# 10_HDMI.net
KiCad netlist of a schematic drawn in Altium Designer
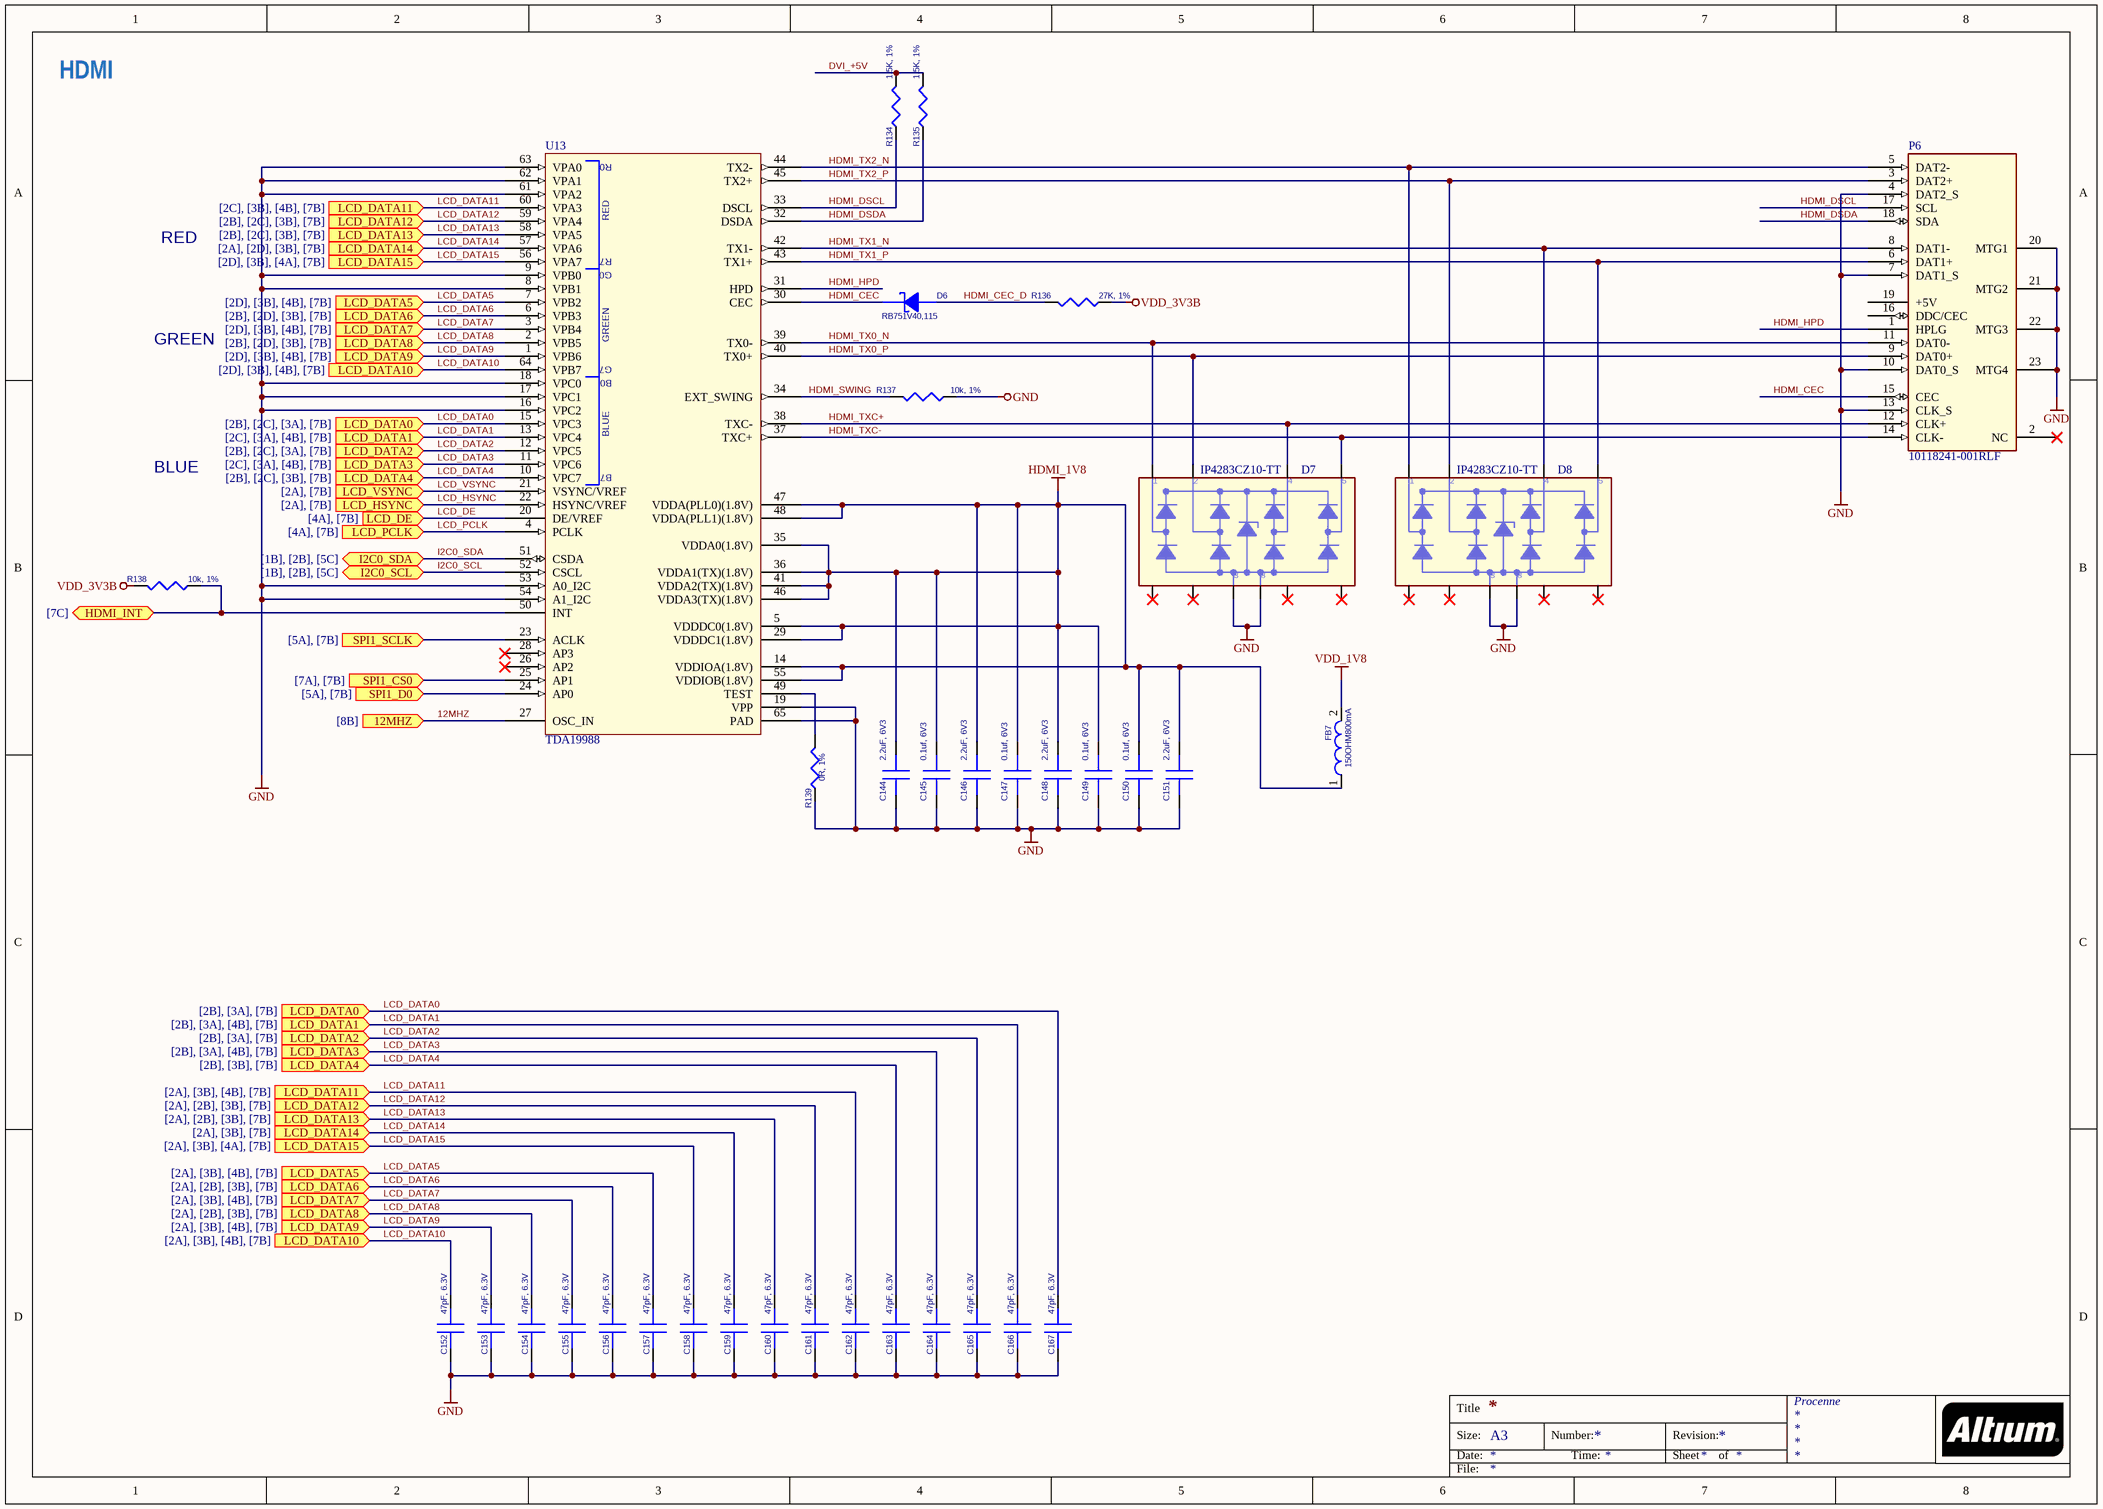
[diagram p0: 10_HDMI.SchDoc]

(export (version "E")
  (design (tool "Eeschema 10.0.6"))
  (components
    (comp (ref "C144")
      (value "2.2uF, 6V3")
      (footprint "402")
      (description "CAP CER 2.2UF 6.3V 10% X5R 0402")
      (fields
        (field (name "MANUFACTURER") "TDK Corporation")
        (field (name "MANUFACTURER PART NUMBER") "C1005X5R0J225K050BC")
      )
      (libsource (lib "BEAGLEBONEBLACK_REV A5B") (part "CAP SMD"))
    )
    (comp (ref "C145")
      (value "0.1uf, 6V3")
      (footprint "402")
      (description "CAP CER 0.1UF 6.3V 10% X5R 0402")
      (fields
        (field (name "MANUFACTURER") "TDK Corporation")
        (field (name "MANUFACTURER PART NUMBER") "C1005X5R0J104K050BA")
      )
      (libsource (lib "BEAGLEBONEBLACK_REV A5B") (part "CAP SMD"))
    )
    (comp (ref "C146")
      (value "2.2uF, 6V3")
      (footprint "402")
      (description "CAP CER 2.2UF 6.3V 10% X5R 0402")
      (fields
        (field (name "MANUFACTURER") "TDK Corporation")
        (field (name "MANUFACTURER PART NUMBER") "C1005X5R0J225K050BC")
      )
      (libsource (lib "BEAGLEBONEBLACK_REV A5B") (part "CAP SMD"))
    )
    (comp (ref "C147")
      (value "0.1uf, 6V3")
      (footprint "402")
      (description "CAP CER 0.1UF 6.3V 10% X5R 0402")
      (fields
        (field (name "MANUFACTURER") "TDK Corporation")
        (field (name "MANUFACTURER PART NUMBER") "C1005X5R0J104K050BA")
      )
      (libsource (lib "BEAGLEBONEBLACK_REV A5B") (part "CAP SMD"))
    )
    (comp (ref "C148")
      (value "2.2uF, 6V3")
      (footprint "402")
      (description "CAP CER 2.2UF 6.3V 10% X5R 0402")
      (fields
        (field (name "MANUFACTURER") "TDK Corporation")
        (field (name "MANUFACTURER PART NUMBER") "C1005X5R0J225K050BC")
      )
      (libsource (lib "BEAGLEBONEBLACK_REV A5B") (part "CAP SMD"))
    )
    (comp (ref "C149")
      (value "0.1uf, 6V3")
      (footprint "402")
      (description "CAP CER 0.1UF 6.3V 10% X5R 0402")
      (fields
        (field (name "MANUFACTURER") "TDK Corporation")
        (field (name "MANUFACTURER PART NUMBER") "C1005X5R0J104K050BA")
      )
      (libsource (lib "BEAGLEBONEBLACK_REV A5B") (part "CAP SMD"))
    )
    (comp (ref "C150")
      (value "0.1uf, 6V3")
      (footprint "402")
      (description "CAP CER 0.1UF 6.3V 10% X5R 0402")
      (fields
        (field (name "MANUFACTURER") "TDK Corporation")
        (field (name "MANUFACTURER PART NUMBER") "C1005X5R0J104K050BA")
      )
      (libsource (lib "BEAGLEBONEBLACK_REV A5B") (part "CAP SMD"))
    )
    (comp (ref "C151")
      (value "2.2uF, 6V3")
      (footprint "402")
      (description "CAP CER 2.2UF 6.3V 10% X5R 0402")
      (fields
        (field (name "MANUFACTURER") "TDK Corporation")
        (field (name "MANUFACTURER PART NUMBER") "C1005X5R0J225K050BC")
      )
      (libsource (lib "BEAGLEBONEBLACK_REV A5B") (part "CAP SMD"))
    )
    (comp (ref "C152")
      (value "47pF, 6.3V")
      (footprint "402")
      (description "CAP CER 47PF 50V 5% NP0 0402")
      (fields
        (field (name "MANUFACTURER") "TDK Corporation")
        (field (name "MANUFACTURER PART NUMBER") "C1005C0G1H470J050BA")
      )
      (libsource (lib "BEAGLEBONEBLACK_REV A5B") (part "CAP SMD"))
    )
    (comp (ref "C153")
      (value "47pF, 6.3V")
      (footprint "402")
      (description "CAP CER 47PF 50V 5% NP0 0402")
      (fields
        (field (name "MANUFACTURER") "TDK Corporation")
        (field (name "MANUFACTURER PART NUMBER") "C1005C0G1H470J050BA")
      )
      (libsource (lib "BEAGLEBONEBLACK_REV A5B") (part "CAP SMD"))
    )
    (comp (ref "C154")
      (value "47pF, 6.3V")
      (footprint "402")
      (description "CAP CER 47PF 50V 5% NP0 0402")
      (fields
        (field (name "MANUFACTURER") "TDK Corporation")
        (field (name "MANUFACTURER PART NUMBER") "C1005C0G1H470J050BA")
      )
      (libsource (lib "BEAGLEBONEBLACK_REV A5B") (part "CAP SMD"))
    )
    (comp (ref "C155")
      (value "47pF, 6.3V")
      (footprint "402")
      (description "CAP CER 47PF 50V 5% NP0 0402")
      (fields
        (field (name "MANUFACTURER") "TDK Corporation")
        (field (name "MANUFACTURER PART NUMBER") "C1005C0G1H470J050BA")
      )
      (libsource (lib "BEAGLEBONEBLACK_REV A5B") (part "CAP SMD"))
    )
    (comp (ref "C156")
      (value "47pF, 6.3V")
      (footprint "402")
      (description "CAP CER 47PF 50V 5% NP0 0402")
      (fields
        (field (name "MANUFACTURER") "TDK Corporation")
        (field (name "MANUFACTURER PART NUMBER") "C1005C0G1H470J050BA")
      )
      (libsource (lib "BEAGLEBONEBLACK_REV A5B") (part "CAP SMD"))
    )
    (comp (ref "C157")
      (value "47pF, 6.3V")
      (footprint "402")
      (description "CAP CER 47PF 50V 5% NP0 0402")
      (fields
        (field (name "MANUFACTURER") "TDK Corporation")
        (field (name "MANUFACTURER PART NUMBER") "C1005C0G1H470J050BA")
      )
      (libsource (lib "BEAGLEBONEBLACK_REV A5B") (part "CAP SMD"))
    )
    (comp (ref "C158")
      (value "47pF, 6.3V")
      (footprint "402")
      (description "CAP CER 47PF 50V 5% NP0 0402")
      (fields
        (field (name "MANUFACTURER") "TDK Corporation")
        (field (name "MANUFACTURER PART NUMBER") "C1005C0G1H470J050BA")
      )
      (libsource (lib "BEAGLEBONEBLACK_REV A5B") (part "CAP SMD"))
    )
    (comp (ref "C159")
      (value "47pF, 6.3V")
      (footprint "402")
      (description "CAP CER 47PF 50V 5% NP0 0402")
      (fields
        (field (name "MANUFACTURER") "TDK Corporation")
        (field (name "MANUFACTURER PART NUMBER") "C1005C0G1H470J050BA")
      )
      (libsource (lib "BEAGLEBONEBLACK_REV A5B") (part "CAP SMD"))
    )
    (comp (ref "C160")
      (value "47pF, 6.3V")
      (footprint "402")
      (description "CAP CER 47PF 50V 5% NP0 0402")
      (fields
        (field (name "MANUFACTURER") "TDK Corporation")
        (field (name "MANUFACTURER PART NUMBER") "C1005C0G1H470J050BA")
      )
      (libsource (lib "BEAGLEBONEBLACK_REV A5B") (part "CAP SMD"))
    )
    (comp (ref "C161")
      (value "47pF, 6.3V")
      (footprint "402")
      (description "CAP CER 47PF 50V 5% NP0 0402")
      (fields
        (field (name "MANUFACTURER") "TDK Corporation")
        (field (name "MANUFACTURER PART NUMBER") "C1005C0G1H470J050BA")
      )
      (libsource (lib "BEAGLEBONEBLACK_REV A5B") (part "CAP SMD"))
    )
    (comp (ref "C162")
      (value "47pF, 6.3V")
      (footprint "402")
      (description "CAP CER 47PF 50V 5% NP0 0402")
      (fields
        (field (name "MANUFACTURER") "TDK Corporation")
        (field (name "MANUFACTURER PART NUMBER") "C1005C0G1H470J050BA")
      )
      (libsource (lib "BEAGLEBONEBLACK_REV A5B") (part "CAP SMD"))
    )
    (comp (ref "C163")
      (value "47pF, 6.3V")
      (footprint "402")
      (description "CAP CER 47PF 50V 5% NP0 0402")
      (fields
        (field (name "MANUFACTURER") "TDK Corporation")
        (field (name "MANUFACTURER PART NUMBER") "C1005C0G1H470J050BA")
      )
      (libsource (lib "BEAGLEBONEBLACK_REV A5B") (part "CAP SMD"))
    )
    (comp (ref "C164")
      (value "47pF, 6.3V")
      (footprint "402")
      (description "CAP CER 47PF 50V 5% NP0 0402")
      (fields
        (field (name "MANUFACTURER") "TDK Corporation")
        (field (name "MANUFACTURER PART NUMBER") "C1005C0G1H470J050BA")
      )
      (libsource (lib "BEAGLEBONEBLACK_REV A5B") (part "CAP SMD"))
    )
    (comp (ref "C165")
      (value "47pF, 6.3V")
      (footprint "402")
      (description "CAP CER 47PF 50V 5% NP0 0402")
      (fields
        (field (name "MANUFACTURER") "TDK Corporation")
        (field (name "MANUFACTURER PART NUMBER") "C1005C0G1H470J050BA")
      )
      (libsource (lib "BEAGLEBONEBLACK_REV A5B") (part "CAP SMD"))
    )
    (comp (ref "C166")
      (value "47pF, 6.3V")
      (footprint "402")
      (description "CAP CER 47PF 50V 5% NP0 0402")
      (fields
        (field (name "MANUFACTURER") "TDK Corporation")
        (field (name "MANUFACTURER PART NUMBER") "C1005C0G1H470J050BA")
      )
      (libsource (lib "BEAGLEBONEBLACK_REV A5B") (part "CAP SMD"))
    )
    (comp (ref "C167")
      (value "47pF, 6.3V")
      (footprint "402")
      (description "CAP CER 47PF 50V 5% NP0 0402")
      (fields
        (field (name "MANUFACTURER") "TDK Corporation")
        (field (name "MANUFACTURER PART NUMBER") "C1005C0G1H470J050BA")
      )
      (libsource (lib "BEAGLEBONEBLACK_REV A5B") (part "CAP SMD"))
    )
    (comp (ref "D6")
      (value "RB751V40,115")
      (footprint "SOD323")
      (description "DIODE SCHOTTKY 40V 120MA SOD323")
      (fields (field (name "MANUFACTURER") "NXP Semiconductors"))
      (libsource (lib "BEAGLEBONEBLACK_REV A5B") (part "Zener"))
    )
    (comp (ref "D7")
      (value "IP4283CZ10-TT")
      (footprint "TSSOP10")
      (description "DIODE ESD PROT HDMI 10TSSOP")
      (fields
        (field (name "MANUFACTURER") "NXP Semiconductors")
        (field (name "MANUFACTURER PART NUMBER") "IP4283CZ10-TT,118")
      )
      (libsource (lib "BEAGLEBONEBLACK_REV A5B") (part "32CTQ030/TO_1"))
    )
    (comp (ref "D8")
      (value "IP4283CZ10-TT")
      (footprint "TSSOP10")
      (description "DIODE ESD PROT HDMI 10TSSOP")
      (fields
        (field (name "MANUFACTURER") "NXP Semiconductors")
        (field (name "MANUFACTURER PART NUMBER") "IP4283CZ10-TT,118")
      )
      (libsource (lib "BEAGLEBONEBLACK_REV A5B") (part "32CTQ030/TO_1"))
    )
    (comp (ref "FB7")
      (value "150OHM800mA")
      (footprint "SM-7351-IND-0805")
      (description "FERRITE 800MA 150 OHM 0805 SMD")
      (fields
        (field (name "MANUFACTURER") "Laird-Signal Integrity Products")
        (field (name "MANUFACTURER PART NUMBER") "LI0805H151R-10")
      )
      (libsource (lib "BEAGLEBONEBLACK_REV A5B") (part "IND"))
    )
    (comp (ref "P6")
      (value "10118241-001RLF")
      (footprint "CONN19_HDMI")
      (description "CONN HDMI RECPT 19POS SMT R/A")
      (fields (field (name "MANUFACTURER") "FCI"))
      (libsource (lib "BEAGLEBONEBLACK_REV A5B") (part "Micro HDMI"))
    )
    (comp (ref "R134")
      (value "1.5K, 1%")
      (footprint "402")
      (description "RES 1.50K OHM 1/16W 1% 0402 SMD")
      (fields
        (field (name "MANUFACTURER") "Yageo")
        (field (name "MANUFACTURER PART NUMBER") "RC0402FR-071K5L")
      )
      (libsource (lib "BEAGLEBONEBLACK_REV A5B") (part "RES SMD"))
    )
    (comp (ref "R135")
      (value "1.5K, 1%")
      (footprint "402")
      (description "RES 1.50K OHM 1/16W 1% 0402 SMD")
      (fields
        (field (name "MANUFACTURER") "Yageo")
        (field (name "MANUFACTURER PART NUMBER") "RC0402FR-071K5L")
      )
      (libsource (lib "BEAGLEBONEBLACK_REV A5B") (part "RES SMD"))
    )
    (comp (ref "R136")
      (value "27K, 1%")
      (footprint "402")
      (description "RES 27.0K OHM 1/16W 1% 0402 SMD")
      (fields
        (field (name "MANUFACTURER") "Yageo")
        (field (name "MANUFACTURER PART NUMBER") "RC0402FR-0727KL")
      )
      (libsource (lib "BEAGLEBONEBLACK_REV A5B") (part "RES SMD"))
    )
    (comp (ref "R137")
      (value "10k, 1%")
      (footprint "402")
      (description "RES 10K OHM 1/16W 5% 0402 SMD")
      (fields
        (field (name "MANUFACTURER") "Rohm Semiconductor")
        (field (name "MANUFACTURER PART NUMBER") "MCR01MZPJ103")
      )
      (libsource (lib "BEAGLEBONEBLACK_REV A5B") (part "RES SMD"))
    )
    (comp (ref "R138")
      (value "10k, 1%")
      (footprint "402")
      (description "RES 10K OHM 1/16W 5% 0402 SMD")
      (fields
        (field (name "MANUFACTURER") "Rohm Semiconductor")
        (field (name "MANUFACTURER PART NUMBER") "MCR01MZPJ103")
      )
      (libsource (lib "BEAGLEBONEBLACK_REV A5B") (part "RES SMD"))
    )
    (comp (ref "R139")
      (value "0R, 1%")
      (footprint "402")
      (description "RES 0.0 OHM 1/16W 0402 SMD")
      (fields
        (field (name "MANUFACTURER") "Yageo")
        (field (name "MANUFACTURER PART NUMBER") "RC0402JR-070RL")
      )
      (libsource (lib "BEAGLEBONEBLACK_REV A5B") (part "RES SMD"))
    )
    (comp (ref "U13")
      (value "TDA19988")
      (footprint "QFN64S9X9P5")
      (description "IC HDMI TRANSMITTER 64-HVQFN")
      (fields
        (field (name "MANUFACTURER") "NXP Semiconductors")
        (field (name "MANUFACTURER PART NUMBER") "TDA19988AHN/C1,551")
      )
      (libsource (lib "BEAGLEBONEBLACK_REV A5B") (part "TDA19988"))
    )
  )
  (nets
    (net (code "1") (name "/12MHZ") (class "Default")
      (node (ref "U13") (pin "27") (pinfunction "OSC_IN_27") (pintype "passive"))
    )
    (net (code "2") (name "/DVI_+5V") (class "Default")
      (node (ref "R134") (pin "1") (pinfunction "P1_1") (pintype "passive"))
      (node (ref "R135") (pin "1") (pinfunction "P1_1") (pintype "passive"))
    )
    (net (code "3") (name "/HDMI_CEC") (class "Default")
      (node (ref "D6") (pin "1") (pinfunction "C_1") (pintype "passive"))
      (node (ref "P6") (pin "15") (pinfunction "CEC_15") (pintype "bidirectional"))
      (node (ref "U13") (pin "30") (pinfunction "CEC_30") (pintype "output"))
    )
    (net (code "4") (name "/HDMI_CEC_D") (class "Default")
      (node (ref "D6") (pin "2") (pinfunction "A_2") (pintype "passive"))
      (node (ref "R136") (pin "1") (pinfunction "P1_1") (pintype "passive"))
    )
    (net (code "5") (name "/HDMI_DSCL") (class "Default")
      (node (ref "P6") (pin "17") (pinfunction "SCL_17") (pintype "input"))
      (node (ref "R134") (pin "2") (pinfunction "P2_2") (pintype "passive"))
      (node (ref "U13") (pin "33") (pinfunction "DSCL_33") (pintype "output"))
    )
    (net (code "6") (name "/HDMI_DSDA") (class "Default")
      (node (ref "P6") (pin "18") (pinfunction "SDA_18") (pintype "bidirectional"))
      (node (ref "R135") (pin "2") (pinfunction "P2_2") (pintype "passive"))
      (node (ref "U13") (pin "32") (pinfunction "DSDA_32") (pintype "output"))
    )
    (net (code "7") (name "/HDMI_HPD") (class "Default")
      (node (ref "P6") (pin "1") (pinfunction "HPLG_1") (pintype "passive"))
      (node (ref "U13") (pin "31") (pinfunction "HPD_31") (pintype "output"))
    )
    (net (code "8") (name "/HDMI_INT") (class "Default")
      (node (ref "R138") (pin "2") (pinfunction "P2_2") (pintype "passive"))
      (node (ref "U13") (pin "50") (pinfunction "INT_50") (pintype "open_collector"))
    )
    (net (code "9") (name "/HDMI_SWING") (class "Default")
      (node (ref "R137") (pin "1") (pinfunction "P1_1") (pintype "passive"))
      (node (ref "U13") (pin "34") (pinfunction "EXT_SWING_34") (pintype "output"))
    )
    (net (code "10") (name "/HDMI_TX0_N") (class "Default")
      (node (ref "D7") (pin "1") (pinfunction "1_1") (pintype "passive"))
      (node (ref "P6") (pin "11") (pinfunction "DAT0-_11") (pintype "input"))
      (node (ref "U13") (pin "39") (pinfunction "TX0-_39") (pintype "output"))
    )
    (net (code "11") (name "/HDMI_TX0_P") (class "Default")
      (node (ref "D7") (pin "2") (pinfunction "2_2") (pintype "passive"))
      (node (ref "P6") (pin "9") (pinfunction "DAT0+_9") (pintype "input"))
      (node (ref "U13") (pin "40") (pinfunction "TX0+_40") (pintype "output"))
    )
    (net (code "12") (name "/HDMI_TX1_N") (class "Default")
      (node (ref "D8") (pin "4") (pinfunction "4_4") (pintype "passive"))
      (node (ref "P6") (pin "8") (pinfunction "DAT1-_8") (pintype "input"))
      (node (ref "U13") (pin "42") (pinfunction "TX1-_42") (pintype "output"))
    )
    (net (code "13") (name "/HDMI_TX1_P") (class "Default")
      (node (ref "D8") (pin "5") (pinfunction "5_5") (pintype "passive"))
      (node (ref "P6") (pin "6") (pinfunction "DAT1+_6") (pintype "input"))
      (node (ref "U13") (pin "43") (pinfunction "TX1+_43") (pintype "output"))
    )
    (net (code "14") (name "/HDMI_TX2_N") (class "Default")
      (node (ref "D8") (pin "1") (pinfunction "1_1") (pintype "passive"))
      (node (ref "P6") (pin "5") (pinfunction "DAT2-_5") (pintype "input"))
      (node (ref "U13") (pin "44") (pinfunction "TX2-_44") (pintype "output"))
    )
    (net (code "15") (name "/HDMI_TX2_P") (class "Default")
      (node (ref "D8") (pin "2") (pinfunction "2_2") (pintype "passive"))
      (node (ref "P6") (pin "3") (pinfunction "DAT2+_3") (pintype "input"))
      (node (ref "U13") (pin "45") (pinfunction "TX2+_45") (pintype "output"))
    )
    (net (code "16") (name "/HDMI_TXC+") (class "Default")
      (node (ref "D7") (pin "4") (pinfunction "4_4") (pintype "passive"))
      (node (ref "P6") (pin "12") (pinfunction "CLK+_12") (pintype "input"))
      (node (ref "U13") (pin "38") (pinfunction "TXC-_38") (pintype "output"))
    )
    (net (code "17") (name "/HDMI_TXC-") (class "Default")
      (node (ref "D7") (pin "5") (pinfunction "5_5") (pintype "passive"))
      (node (ref "P6") (pin "14") (pinfunction "CLK-_14") (pintype "input"))
      (node (ref "U13") (pin "37") (pinfunction "TXC+_37") (pintype "output"))
    )
    (net (code "18") (name "/I2C0_SCL") (class "Default")
      (node (ref "U13") (pin "52") (pinfunction "CSCL_52") (pintype "input"))
    )
    (net (code "19") (name "/I2C0_SDA") (class "Default")
      (node (ref "U13") (pin "51") (pinfunction "CSDA_51") (pintype "bidirectional"))
    )
    (net (code "20") (name "/LCD_DATA0") (class "Default")
      (node (ref "C167") (pin "1") (pinfunction "1_1") (pintype "passive"))
      (node (ref "U13") (pin "15") (pinfunction "VPC3_15") (pintype "input"))
    )
    (net (code "21") (name "/LCD_DATA1") (class "Default")
      (node (ref "C166") (pin "1") (pinfunction "1_1") (pintype "passive"))
      (node (ref "U13") (pin "13") (pinfunction "VPC4_13") (pintype "input"))
    )
    (net (code "22") (name "/LCD_DATA2") (class "Default")
      (node (ref "C165") (pin "1") (pinfunction "1_1") (pintype "passive"))
      (node (ref "U13") (pin "12") (pinfunction "VPC5_12") (pintype "input"))
    )
    (net (code "23") (name "/LCD_DATA3") (class "Default")
      (node (ref "C164") (pin "1") (pinfunction "1_1") (pintype "passive"))
      (node (ref "U13") (pin "11") (pinfunction "VPC6_11") (pintype "input"))
    )
    (net (code "24") (name "/LCD_DATA4") (class "Default")
      (node (ref "C163") (pin "1") (pinfunction "1_1") (pintype "passive"))
      (node (ref "U13") (pin "10") (pinfunction "VPC7_10") (pintype "input"))
    )
    (net (code "25") (name "/LCD_DATA5") (class "Default")
      (node (ref "C157") (pin "1") (pinfunction "1_1") (pintype "passive"))
      (node (ref "U13") (pin "7") (pinfunction "VPB2_7") (pintype "input"))
    )
    (net (code "26") (name "/LCD_DATA6") (class "Default")
      (node (ref "C156") (pin "1") (pinfunction "1_1") (pintype "passive"))
      (node (ref "U13") (pin "6") (pinfunction "VPB3_6") (pintype "input"))
    )
    (net (code "27") (name "/LCD_DATA7") (class "Default")
      (node (ref "C155") (pin "1") (pinfunction "1_1") (pintype "passive"))
      (node (ref "U13") (pin "3") (pinfunction "VPB4_3") (pintype "input"))
    )
    (net (code "28") (name "/LCD_DATA8") (class "Default")
      (node (ref "C154") (pin "1") (pinfunction "1_1") (pintype "passive"))
      (node (ref "U13") (pin "2") (pinfunction "VPB5_2") (pintype "input"))
    )
    (net (code "29") (name "/LCD_DATA9") (class "Default")
      (node (ref "C153") (pin "1") (pinfunction "1_1") (pintype "passive"))
      (node (ref "U13") (pin "1") (pinfunction "VPB6_1") (pintype "input"))
    )
    (net (code "30") (name "/LCD_DATA10") (class "Default")
      (node (ref "C152") (pin "1") (pinfunction "1_1") (pintype "passive"))
      (node (ref "U13") (pin "64") (pinfunction "VPB7_64") (pintype "input"))
    )
    (net (code "31") (name "/LCD_DATA11") (class "Default")
      (node (ref "C162") (pin "1") (pinfunction "1_1") (pintype "passive"))
      (node (ref "U13") (pin "60") (pinfunction "VPA3_60") (pintype "input"))
    )
    (net (code "32") (name "/LCD_DATA12") (class "Default")
      (node (ref "C161") (pin "1") (pinfunction "1_1") (pintype "passive"))
      (node (ref "U13") (pin "59") (pinfunction "VPA4_59") (pintype "input"))
    )
    (net (code "33") (name "/LCD_DATA13") (class "Default")
      (node (ref "C160") (pin "1") (pinfunction "1_1") (pintype "passive"))
      (node (ref "U13") (pin "58") (pinfunction "VPA5_58") (pintype "input"))
    )
    (net (code "34") (name "/LCD_DATA14") (class "Default")
      (node (ref "C159") (pin "1") (pinfunction "1_1") (pintype "passive"))
      (node (ref "U13") (pin "57") (pinfunction "VPA6_57") (pintype "input"))
    )
    (net (code "35") (name "/LCD_DATA15") (class "Default")
      (node (ref "C158") (pin "1") (pinfunction "1_1") (pintype "passive"))
      (node (ref "U13") (pin "56") (pinfunction "VPA7_56") (pintype "input"))
    )
    (net (code "36") (name "/LCD_DE") (class "Default")
      (node (ref "U13") (pin "20") (pinfunction "DE/VREF_20") (pintype "passive"))
    )
    (net (code "37") (name "/LCD_HSYNC") (class "Default")
      (node (ref "U13") (pin "22") (pinfunction "HSYNC/VREF_22") (pintype "input"))
    )
    (net (code "38") (name "/LCD_PCLK") (class "Default")
      (node (ref "U13") (pin "4") (pinfunction "PCLK_4") (pintype "input"))
    )
    (net (code "39") (name "/LCD_VSYNC") (class "Default")
      (node (ref "U13") (pin "21") (pinfunction "VSYNC/VREF_21") (pintype "input"))
    )
    (net (code "40") (name "/SPI1_CS0") (class "Default")
      (node (ref "U13") (pin "25") (pinfunction "AP1_25") (pintype "input"))
    )
    (net (code "41") (name "/SPI1_D0") (class "Default")
      (node (ref "U13") (pin "24") (pinfunction "AP0_24") (pintype "input"))
    )
    (net (code "42") (name "/SPI1_SCLK") (class "Default")
      (node (ref "U13") (pin "23") (pinfunction "ACLK_23") (pintype "input"))
    )
    (net (code "43") (name "GND") (class "Default")
      (node (ref "C144") (pin "2") (pinfunction "2_2") (pintype "passive"))
      (node (ref "C145") (pin "2") (pinfunction "2_2") (pintype "passive"))
      (node (ref "C146") (pin "2") (pinfunction "2_2") (pintype "passive"))
      (node (ref "C147") (pin "2") (pinfunction "2_2") (pintype "passive"))
      (node (ref "C148") (pin "2") (pinfunction "2_2") (pintype "passive"))
      (node (ref "C149") (pin "2") (pinfunction "2_2") (pintype "passive"))
      (node (ref "C150") (pin "2") (pinfunction "2_2") (pintype "passive"))
      (node (ref "C151") (pin "2") (pinfunction "2_2") (pintype "passive"))
      (node (ref "C152") (pin "2") (pinfunction "2_2") (pintype "passive"))
      (node (ref "C153") (pin "2") (pinfunction "2_2") (pintype "passive"))
      (node (ref "C154") (pin "2") (pinfunction "2_2") (pintype "passive"))
      (node (ref "C155") (pin "2") (pinfunction "2_2") (pintype "passive"))
      (node (ref "C156") (pin "2") (pinfunction "2_2") (pintype "passive"))
      (node (ref "C157") (pin "2") (pinfunction "2_2") (pintype "passive"))
      (node (ref "C158") (pin "2") (pinfunction "2_2") (pintype "passive"))
      (node (ref "C159") (pin "2") (pinfunction "2_2") (pintype "passive"))
      (node (ref "C160") (pin "2") (pinfunction "2_2") (pintype "passive"))
      (node (ref "C161") (pin "2") (pinfunction "2_2") (pintype "passive"))
      (node (ref "C162") (pin "2") (pinfunction "2_2") (pintype "passive"))
      (node (ref "C163") (pin "2") (pinfunction "2_2") (pintype "passive"))
      (node (ref "C164") (pin "2") (pinfunction "2_2") (pintype "passive"))
      (node (ref "C165") (pin "2") (pinfunction "2_2") (pintype "passive"))
      (node (ref "C166") (pin "2") (pinfunction "2_2") (pintype "passive"))
      (node (ref "C167") (pin "2") (pinfunction "2_2") (pintype "passive"))
      (node (ref "D7") (pin "3") (pinfunction "3_3") (pintype "passive"))
      (node (ref "D7") (pin "8") (pinfunction "8_8") (pintype "passive"))
      (node (ref "D8") (pin "3") (pinfunction "3_3") (pintype "passive"))
      (node (ref "D8") (pin "8") (pinfunction "8_8") (pintype "passive"))
      (node (ref "P6") (pin "10") (pinfunction "DAT0_S_10") (pintype "input"))
      (node (ref "P6") (pin "13") (pinfunction "CLK_S_13") (pintype "input"))
      (node (ref "P6") (pin "20") (pinfunction "MTG1_20") (pintype "passive"))
      (node (ref "P6") (pin "21") (pinfunction "MTG2_21") (pintype "passive"))
      (node (ref "P6") (pin "22") (pinfunction "MTG3_22") (pintype "passive"))
      (node (ref "P6") (pin "23") (pinfunction "MTG4_23") (pintype "passive"))
      (node (ref "P6") (pin "4") (pinfunction "DAT2_S_4") (pintype "input"))
      (node (ref "P6") (pin "7") (pinfunction "DAT1_S_7") (pintype "input"))
      (node (ref "R137") (pin "2") (pinfunction "P2_2") (pintype "passive"))
      (node (ref "R139") (pin "2") (pinfunction "P2_2") (pintype "passive"))
      (node (ref "U13") (pin "16") (pinfunction "VPC2_16") (pintype "input"))
      (node (ref "U13") (pin "17") (pinfunction "VPC1_17") (pintype "input"))
      (node (ref "U13") (pin "18") (pinfunction "VPC0_18") (pintype "input"))
      (node (ref "U13") (pin "19") (pinfunction "VPP_19") (pintype "power_in"))
      (node (ref "U13") (pin "53") (pinfunction "A0_I2C_53") (pintype "input"))
      (node (ref "U13") (pin "54") (pinfunction "A1_I2C_54") (pintype "input"))
      (node (ref "U13") (pin "61") (pinfunction "VPA2_61") (pintype "input"))
      (node (ref "U13") (pin "62") (pinfunction "VPA1_62") (pintype "input"))
      (node (ref "U13") (pin "63") (pinfunction "VPA0_63") (pintype "input"))
      (node (ref "U13") (pin "65") (pinfunction "PAD_65") (pintype "power_in"))
      (node (ref "U13") (pin "8") (pinfunction "VPB1_8") (pintype "input"))
      (node (ref "U13") (pin "9") (pinfunction "VPB0_9") (pintype "input"))
    )
    (net (code "44") (name "HDMI_1V8") (class "Default")
      (node (ref "C144") (pin "1") (pinfunction "1_1") (pintype "passive"))
      (node (ref "C145") (pin "1") (pinfunction "1_1") (pintype "passive"))
      (node (ref "C146") (pin "1") (pinfunction "1_1") (pintype "passive"))
      (node (ref "C147") (pin "1") (pinfunction "1_1") (pintype "passive"))
      (node (ref "C148") (pin "1") (pinfunction "1_1") (pintype "passive"))
      (node (ref "C149") (pin "1") (pinfunction "1_1") (pintype "passive"))
      (node (ref "C150") (pin "1") (pinfunction "1_1") (pintype "passive"))
      (node (ref "C151") (pin "1") (pinfunction "1_1") (pintype "passive"))
      (node (ref "FB7") (pin "1") (pinfunction "1_1") (pintype "passive"))
      (node (ref "U13") (pin "14") (pinfunction "VDDIOA(1.8V)_14") (pintype "power_in"))
      (node (ref "U13") (pin "29") (pinfunction "VDDDC1(1.8V)_29") (pintype "power_in"))
      (node (ref "U13") (pin "35") (pinfunction "VDDA0(1.8V)_35") (pintype "power_in"))
      (node (ref "U13") (pin "36") (pinfunction "VDDA1(TX)(1.8V)_36") (pintype "power_in"))
      (node (ref "U13") (pin "41") (pinfunction "VDDA2(TX)(1.8V)_41") (pintype "power_in"))
      (node (ref "U13") (pin "46") (pinfunction "VDDA3(TX)(1.8V)_46") (pintype "power_in"))
      (node (ref "U13") (pin "47") (pinfunction "VDDA(PLL0)(1.8V)_47") (pintype "power_in"))
      (node (ref "U13") (pin "48") (pinfunction "VDDA(PLL1)(1.8V)_48") (pintype "power_in"))
      (node (ref "U13") (pin "5") (pinfunction "VDDDC0(1.8V)_5") (pintype "power_in"))
      (node (ref "U13") (pin "55") (pinfunction "VDDIOB(1.8V)_55") (pintype "power_in"))
    )
    (net (code "45") (name "Net-(R139-P1)") (class "Default")
      (node (ref "R139") (pin "1") (pinfunction "P1_1") (pintype "passive"))
      (node (ref "U13") (pin "49") (pinfunction "TEST_49") (pintype "passive"))
    )
    (net (code "46") (name "VDD_1V8") (class "Default")
      (node (ref "FB7") (pin "2") (pinfunction "2_2") (pintype "passive"))
    )
    (net (code "47") (name "VDD_3V3B") (class "Default")
      (node (ref "R136") (pin "2") (pinfunction "P2_2") (pintype "passive"))
      (node (ref "R138") (pin "1") (pinfunction "P1_1") (pintype "passive"))
    )
    (net (code "48") (name "unconnected-(D7-Pad6)") (class "Default")
      (node (ref "D7") (pin "6") (pinfunction "6_6") (pintype "passive+no_connect"))
    )
    (net (code "49") (name "unconnected-(D7-Pad7)") (class "Default")
      (node (ref "D7") (pin "7") (pinfunction "7_7") (pintype "passive+no_connect"))
    )
    (net (code "50") (name "unconnected-(D7-Pad9)") (class "Default")
      (node (ref "D7") (pin "9") (pinfunction "9_9") (pintype "passive+no_connect"))
    )
    (net (code "51") (name "unconnected-(D7-Pad10)") (class "Default")
      (node (ref "D7") (pin "10") (pinfunction "10_10") (pintype "passive+no_connect"))
    )
    (net (code "52") (name "unconnected-(D8-Pad6)") (class "Default")
      (node (ref "D8") (pin "6") (pinfunction "6_6") (pintype "passive+no_connect"))
    )
    (net (code "53") (name "unconnected-(D8-Pad7)") (class "Default")
      (node (ref "D8") (pin "7") (pinfunction "7_7") (pintype "passive+no_connect"))
    )
    (net (code "54") (name "unconnected-(D8-Pad9)") (class "Default")
      (node (ref "D8") (pin "9") (pinfunction "9_9") (pintype "passive+no_connect"))
    )
    (net (code "55") (name "unconnected-(D8-Pad10)") (class "Default")
      (node (ref "D8") (pin "10") (pinfunction "10_10") (pintype "passive+no_connect"))
    )
    (net (code "56") (name "unconnected-(P6-+5V-Pad19)") (class "Default")
      (node (ref "P6") (pin "19") (pinfunction "+5V_19") (pintype "power_in"))
    )
    (net (code "57") (name "unconnected-(P6-DDC{slash}CEC-Pad16)") (class "Default")
      (node (ref "P6") (pin "16") (pinfunction "DDC/CEC_16") (pintype "bidirectional"))
    )
    (net (code "58") (name "unconnected-(P6-NC-Pad2)") (class "Default")
      (node (ref "P6") (pin "2") (pinfunction "NC_2") (pintype "passive+no_connect"))
    )
    (net (code "59") (name "unconnected-(U13-AP2-Pad26)") (class "Default")
      (node (ref "U13") (pin "26") (pinfunction "AP2_26") (pintype "input+no_connect"))
    )
    (net (code "60") (name "unconnected-(U13-AP3-Pad28)") (class "Default")
      (node (ref "U13") (pin "28") (pinfunction "AP3_28") (pintype "input+no_connect"))
    )
  )
)
